# Mako_DSP_Power.net
KiCad netlist of a schematic drawn in Altium Designer
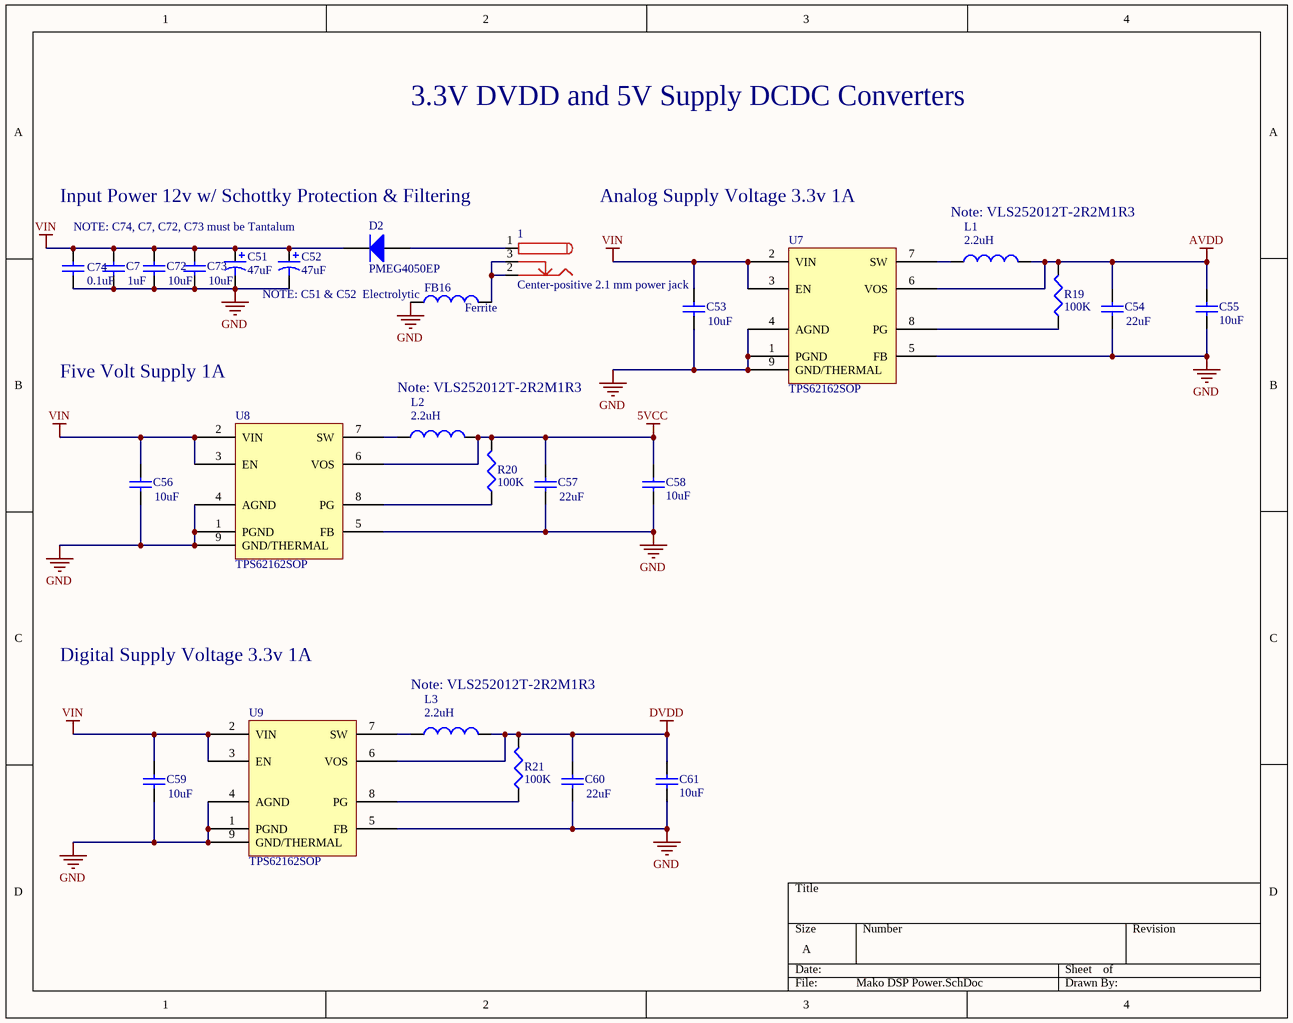
[diagram p0: Mako DSP Power.SchDoc]

(export (version "E")
  (design (tool "Eeschema 10.0.6"))
  (components
    (comp (ref "1")
      (value "Center-positive 2.1 mm power jack")
      (footprint "PJ-102AH")
      (description "Power jack")
      (fields (field (name "PUBLISHER") "Altium Limited"))
      (libsource (lib "Rascal") (part "PWR2.5"))
    )
    (comp (ref "C7")
      (value "1uF")
      (footprint "C1206")
      (description "Capacitor (Semiconductor SIM Model)")
      (fields (field (name "Comment") "Cap Semi") (field (name "PUBLISHER") "Altium Limited"))
      (libsource (lib "Miscellaneous Devices") (part "Cap Semi"))
    )
    (comp (ref "C51")
      (value "47uF")
      (footprint "CAPPR2.5-6.3x5")
      (description "Polarized Capacitor (Radial)")
      (fields (field (name "Comment") "Cap Pol1") (field (name "PUBLISHER") "Altium Limited"))
      (libsource (lib "Miscellaneous Devices") (part "Cap Pol1"))
    )
    (comp (ref "C52")
      (value "47uF")
      (footprint "CAPPR2.5-6.3x5")
      (description "Polarized Capacitor (Radial)")
      (fields (field (name "Comment") "Cap Pol1") (field (name "PUBLISHER") "Altium Limited"))
      (libsource (lib "Miscellaneous Devices") (part "Cap Pol1"))
    )
    (comp (ref "C53")
      (value "10uF")
      (footprint "C1206")
      (description "Capacitor (Semiconductor SIM Model)")
      (fields (field (name "Comment") "Cap Semi") (field (name "PUBLISHER") "Altium Limited"))
      (libsource (lib "Miscellaneous Devices") (part "Cap Semi"))
    )
    (comp (ref "C54")
      (value "22uF")
      (footprint "C1206")
      (description "Capacitor (Semiconductor SIM Model)")
      (fields (field (name "Comment") "Cap Semi") (field (name "PUBLISHER") "Altium Limited"))
      (libsource (lib "Miscellaneous Devices") (part "Cap Semi"))
    )
    (comp (ref "C55")
      (value "10uF")
      (footprint "Panasonic VS B")
      (description "Capacitor (Semiconductor SIM Model)")
      (fields (field (name "Comment") "Cap Semi") (field (name "PUBLISHER") "Altium Limited"))
      (libsource (lib "Miscellaneous Devices") (part "Cap Semi"))
    )
    (comp (ref "C56")
      (value "10uF")
      (footprint "C1206")
      (description "Capacitor (Semiconductor SIM Model)")
      (fields (field (name "Comment") "Cap Semi") (field (name "PUBLISHER") "Altium Limited"))
      (libsource (lib "Miscellaneous Devices") (part "Cap Semi"))
    )
    (comp (ref "C57")
      (value "22uF")
      (footprint "C1206")
      (description "Capacitor (Semiconductor SIM Model)")
      (fields (field (name "Comment") "Cap Semi") (field (name "PUBLISHER") "Altium Limited"))
      (libsource (lib "Miscellaneous Devices") (part "Cap Semi"))
    )
    (comp (ref "C58")
      (value "10uF")
      (footprint "Panasonic VS B")
      (description "Capacitor (Semiconductor SIM Model)")
      (fields (field (name "Comment") "Cap Semi") (field (name "PUBLISHER") "Altium Limited"))
      (libsource (lib "Miscellaneous Devices") (part "Cap Semi"))
    )
    (comp (ref "C59")
      (value "10uF")
      (footprint "C1206")
      (description "Capacitor (Semiconductor SIM Model)")
      (fields (field (name "Comment") "Cap Semi") (field (name "PUBLISHER") "Altium Limited"))
      (libsource (lib "Miscellaneous Devices") (part "Cap Semi"))
    )
    (comp (ref "C60")
      (value "22uF")
      (footprint "C1206")
      (description "Capacitor (Semiconductor SIM Model)")
      (fields (field (name "Comment") "Cap Semi") (field (name "PUBLISHER") "Altium Limited"))
      (libsource (lib "Miscellaneous Devices") (part "Cap Semi"))
    )
    (comp (ref "C61")
      (value "10uF")
      (footprint "Panasonic VS B")
      (description "Capacitor (Semiconductor SIM Model)")
      (fields (field (name "Comment") "Cap Semi") (field (name "PUBLISHER") "Altium Limited"))
      (libsource (lib "Miscellaneous Devices") (part "Cap Semi"))
    )
    (comp (ref "C72")
      (value "10uF")
      (footprint "C1206")
      (description "Capacitor (Semiconductor SIM Model)")
      (fields (field (name "Comment") "Cap Semi") (field (name "PUBLISHER") "Altium Limited"))
      (libsource (lib "Miscellaneous Devices") (part "Cap Semi"))
    )
    (comp (ref "C73")
      (value "10uF")
      (footprint "C1206")
      (description "Capacitor (Semiconductor SIM Model)")
      (fields (field (name "Comment") "Cap Semi") (field (name "PUBLISHER") "Altium Limited"))
      (libsource (lib "Miscellaneous Devices") (part "Cap Semi"))
    )
    (comp (ref "C74")
      (value "0.1uF")
      (footprint "C1206")
      (description "Capacitor (Semiconductor SIM Model)")
      (fields (field (name "Comment") "Cap Semi") (field (name "PUBLISHER") "Altium Limited"))
      (libsource (lib "Miscellaneous Devices") (part "Cap Semi"))
    )
    (comp (ref "D2")
      (value "PMEG4050EP")
      (footprint "PMEG4050EP")
      (description "Default Diode")
      (fields (field (name "PUBLISHER") "Altium Limited"))
      (libsource (lib "Miscellaneous Devices") (part "Diode"))
    )
    (comp (ref "FB16")
      (value "Ferrite")
      (footprint "SM 0805 - gap trimmed")
      (description "Inductor")
      (fields (field (name "PUBLISHER") "Altium Limited"))
      (libsource (lib "Miscellaneous Devices") (part "Inductor"))
    )
    (comp (ref "L1")
      (value "2.2uH")
      (footprint "VLS252012T-2R2M1R3")
      (description "Inductor")
      (fields (field (name "PUBLISHER") "Altium Limited"))
      (libsource (lib "Miscellaneous Devices") (part "Inductor"))
    )
    (comp (ref "L2")
      (value "2.2uH")
      (footprint "VLS252012T-2R2M1R3")
      (description "Inductor")
      (fields (field (name "PUBLISHER") "Altium Limited"))
      (libsource (lib "Miscellaneous Devices") (part "Inductor"))
    )
    (comp (ref "L3")
      (value "2.2uH")
      (footprint "VLS252012T-2R2M1R3")
      (description "Inductor")
      (fields (field (name "PUBLISHER") "Altium Limited"))
      (libsource (lib "Miscellaneous Devices") (part "Inductor"))
    )
    (comp (ref "R19")
      (value "100K")
      (footprint "RESC2012L")
      (description "Resistor")
      (fields (field (name "Comment") "Res3") (field (name "PUBLISHER") "Altium Limited"))
      (libsource (lib "Miscellaneous Devices") (part "Res3"))
    )
    (comp (ref "R20")
      (value "100K")
      (footprint "RESC2012L")
      (description "Resistor")
      (fields (field (name "Comment") "Res3") (field (name "PUBLISHER") "Altium Limited"))
      (libsource (lib "Miscellaneous Devices") (part "Res3"))
    )
    (comp (ref "R21")
      (value "100K")
      (footprint "RESC2012L")
      (description "Resistor")
      (fields (field (name "Comment") "Res3") (field (name "PUBLISHER") "Altium Limited"))
      (libsource (lib "Miscellaneous Devices") (part "Res3"))
    )
    (comp (ref "U7")
      (value "TPS62162SOP")
      (footprint "TPS62162SOP")
      (libsource (lib "Adams Altium Library") (part "TPS62162SOP"))
    )
    (comp (ref "U8")
      (value "TPS62162SOP")
      (footprint "TPS62162SOP")
      (libsource (lib "Adams Altium Library") (part "TPS62162SOP"))
    )
    (comp (ref "U9")
      (value "TPS62162SOP")
      (footprint "TPS62162SOP")
      (libsource (lib "Adams Altium Library") (part "TPS62162SOP"))
    )
  )
  (nets
    (net (code "1") (name "5VCC") (class "Default")
      (node (ref "C57") (pin "2") (pinfunction "2_2") (pintype "passive"))
      (node (ref "C58") (pin "1") (pinfunction "1_1") (pintype "passive"))
      (node (ref "L2") (pin "2") (pinfunction "2_2") (pintype "passive"))
      (node (ref "R20") (pin "2") (pinfunction "2_2") (pintype "passive"))
      (node (ref "U8") (pin "6") (pinfunction "VOS_6") (pintype "passive"))
    )
    (net (code "2") (name "AVDD") (class "Default")
      (node (ref "C54") (pin "2") (pinfunction "2_2") (pintype "passive"))
      (node (ref "C55") (pin "1") (pinfunction "1_1") (pintype "passive"))
      (node (ref "L1") (pin "2") (pinfunction "2_2") (pintype "passive"))
      (node (ref "R19") (pin "2") (pinfunction "2_2") (pintype "passive"))
      (node (ref "U7") (pin "6") (pinfunction "VOS_6") (pintype "passive"))
    )
    (net (code "3") (name "DVDD") (class "Default")
      (node (ref "C60") (pin "2") (pinfunction "2_2") (pintype "passive"))
      (node (ref "C61") (pin "1") (pinfunction "1_1") (pintype "passive"))
      (node (ref "L3") (pin "2") (pinfunction "2_2") (pintype "passive"))
      (node (ref "R21") (pin "2") (pinfunction "2_2") (pintype "passive"))
      (node (ref "U9") (pin "6") (pinfunction "VOS_6") (pintype "passive"))
    )
    (net (code "4") (name "GND") (class "Default")
      (node (ref "C51") (pin "2") (pinfunction "2_2") (pintype "passive"))
      (node (ref "C52") (pin "2") (pinfunction "2_2") (pintype "passive"))
      (node (ref "C53") (pin "1") (pinfunction "1_1") (pintype "passive"))
      (node (ref "C54") (pin "1") (pinfunction "1_1") (pintype "passive"))
      (node (ref "C55") (pin "2") (pinfunction "2_2") (pintype "passive"))
      (node (ref "C56") (pin "1") (pinfunction "1_1") (pintype "passive"))
      (node (ref "C57") (pin "1") (pinfunction "1_1") (pintype "passive"))
      (node (ref "C58") (pin "2") (pinfunction "2_2") (pintype "passive"))
      (node (ref "C59") (pin "1") (pinfunction "1_1") (pintype "passive"))
      (node (ref "C60") (pin "1") (pinfunction "1_1") (pintype "passive"))
      (node (ref "C61") (pin "2") (pinfunction "2_2") (pintype "passive"))
      (node (ref "C7") (pin "1") (pinfunction "1_1") (pintype "passive"))
      (node (ref "C72") (pin "1") (pinfunction "1_1") (pintype "passive"))
      (node (ref "C73") (pin "1") (pinfunction "1_1") (pintype "passive"))
      (node (ref "C74") (pin "1") (pinfunction "1_1") (pintype "passive"))
      (node (ref "FB16") (pin "1") (pinfunction "1_1") (pintype "passive"))
      (node (ref "U7") (pin "1") (pinfunction "PGND_1") (pintype "passive"))
      (node (ref "U7") (pin "4") (pinfunction "AGND_4") (pintype "passive"))
      (node (ref "U7") (pin "5") (pinfunction "FB_5") (pintype "passive"))
      (node (ref "U7") (pin "9") (pinfunction "GND/THERMAL_9") (pintype "passive"))
      (node (ref "U8") (pin "1") (pinfunction "PGND_1") (pintype "passive"))
      (node (ref "U8") (pin "4") (pinfunction "AGND_4") (pintype "passive"))
      (node (ref "U8") (pin "5") (pinfunction "FB_5") (pintype "passive"))
      (node (ref "U8") (pin "9") (pinfunction "GND/THERMAL_9") (pintype "passive"))
      (node (ref "U9") (pin "1") (pinfunction "PGND_1") (pintype "passive"))
      (node (ref "U9") (pin "4") (pinfunction "AGND_4") (pintype "passive"))
      (node (ref "U9") (pin "5") (pinfunction "FB_5") (pintype "passive"))
      (node (ref "U9") (pin "9") (pinfunction "GND/THERMAL_9") (pintype "passive"))
    )
    (net (code "5") (name "Net-(1-Pad2)") (class "Default")
      (node (ref "1") (pin "2") (pinfunction "2_2") (pintype "power_in"))
      (node (ref "1") (pin "3") (pinfunction "3_3") (pintype "power_in"))
      (node (ref "FB16") (pin "2") (pinfunction "2_2") (pintype "passive"))
    )
    (net (code "6") (name "Net-(D2-K)") (class "Default")
      (node (ref "1") (pin "1") (pinfunction "1_1") (pintype "power_in"))
      (node (ref "D2") (pin "2") (pinfunction "K_2") (pintype "passive"))
    )
    (net (code "7") (name "Net-(U7-PG)") (class "Default")
      (node (ref "R19") (pin "1") (pinfunction "1_1") (pintype "passive"))
      (node (ref "U7") (pin "8") (pinfunction "PG_8") (pintype "passive"))
    )
    (net (code "8") (name "Net-(U7-SW)") (class "Default")
      (node (ref "L1") (pin "1") (pinfunction "1_1") (pintype "passive"))
      (node (ref "U7") (pin "7") (pinfunction "SW_7") (pintype "passive"))
    )
    (net (code "9") (name "Net-(U8-PG)") (class "Default")
      (node (ref "R20") (pin "1") (pinfunction "1_1") (pintype "passive"))
      (node (ref "U8") (pin "8") (pinfunction "PG_8") (pintype "passive"))
    )
    (net (code "10") (name "Net-(U8-SW)") (class "Default")
      (node (ref "L2") (pin "1") (pinfunction "1_1") (pintype "passive"))
      (node (ref "U8") (pin "7") (pinfunction "SW_7") (pintype "passive"))
    )
    (net (code "11") (name "Net-(U9-PG)") (class "Default")
      (node (ref "R21") (pin "1") (pinfunction "1_1") (pintype "passive"))
      (node (ref "U9") (pin "8") (pinfunction "PG_8") (pintype "passive"))
    )
    (net (code "12") (name "Net-(U9-SW)") (class "Default")
      (node (ref "L3") (pin "1") (pinfunction "1_1") (pintype "passive"))
      (node (ref "U9") (pin "7") (pinfunction "SW_7") (pintype "passive"))
    )
    (net (code "13") (name "VIN") (class "Default")
      (node (ref "C51") (pin "1") (pinfunction "1_1") (pintype "passive"))
      (node (ref "C52") (pin "1") (pinfunction "1_1") (pintype "passive"))
      (node (ref "C53") (pin "2") (pinfunction "2_2") (pintype "passive"))
      (node (ref "C56") (pin "2") (pinfunction "2_2") (pintype "passive"))
      (node (ref "C59") (pin "2") (pinfunction "2_2") (pintype "passive"))
      (node (ref "C7") (pin "2") (pinfunction "2_2") (pintype "passive"))
      (node (ref "C72") (pin "2") (pinfunction "2_2") (pintype "passive"))
      (node (ref "C73") (pin "2") (pinfunction "2_2") (pintype "passive"))
      (node (ref "C74") (pin "2") (pinfunction "2_2") (pintype "passive"))
      (node (ref "D2") (pin "1") (pinfunction "A_1") (pintype "passive"))
      (node (ref "U7") (pin "2") (pinfunction "VIN_2") (pintype "passive"))
      (node (ref "U7") (pin "3") (pinfunction "EN_3") (pintype "passive"))
      (node (ref "U8") (pin "2") (pinfunction "VIN_2") (pintype "passive"))
      (node (ref "U8") (pin "3") (pinfunction "EN_3") (pintype "passive"))
      (node (ref "U9") (pin "2") (pinfunction "VIN_2") (pintype "passive"))
      (node (ref "U9") (pin "3") (pinfunction "EN_3") (pintype "passive"))
    )
  )
)
